# RasPi-BplusHAT.net
KiCad netlist of a schematic drawn in EAGLE
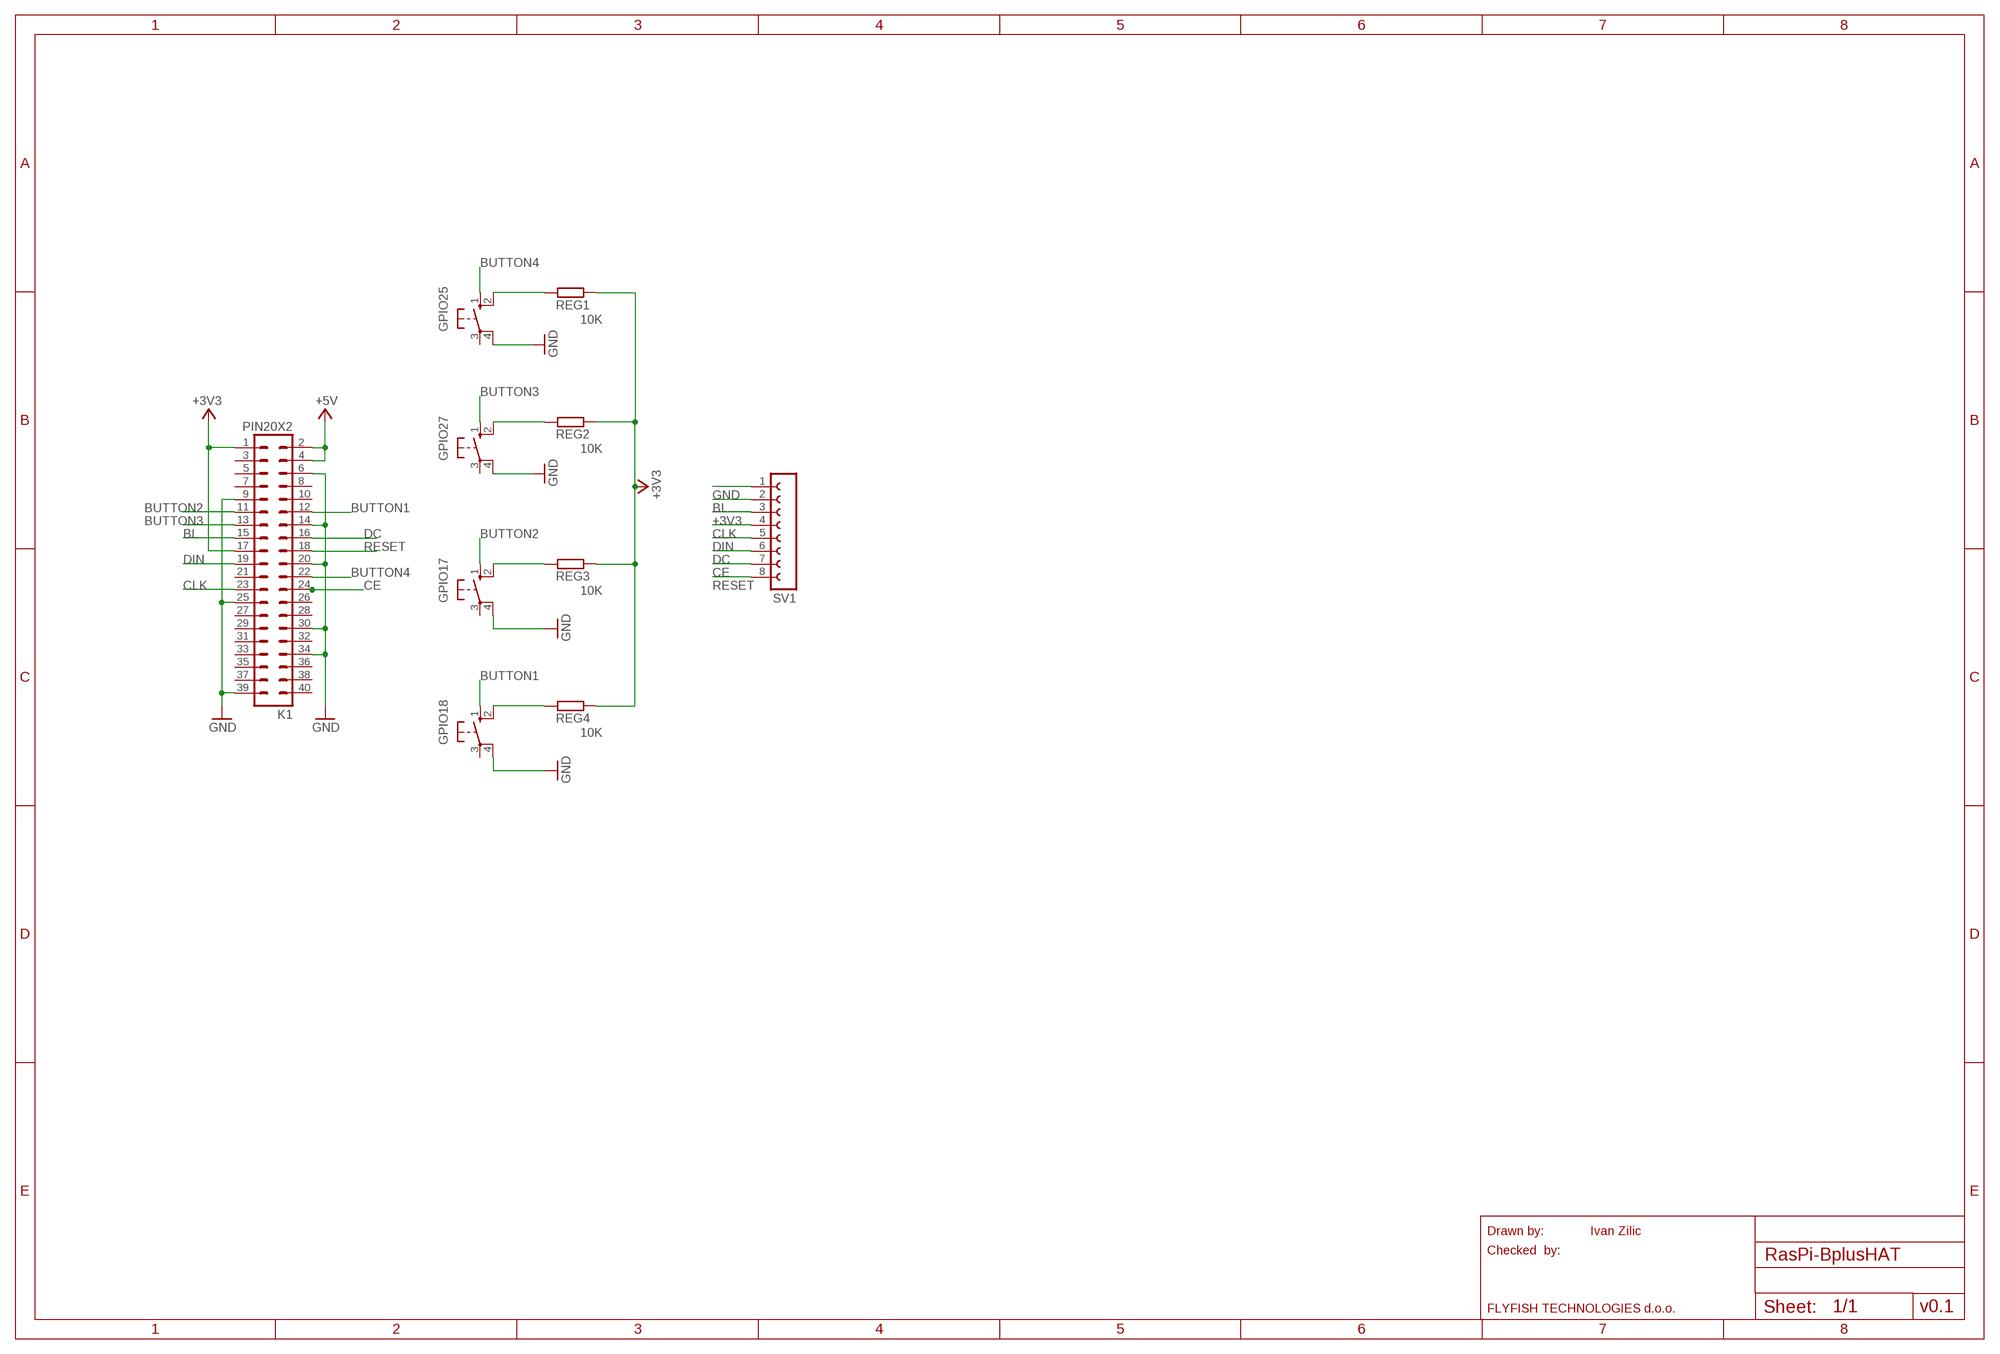
[diagram p0: schematic, sheet 1]

(export (version "E")
  (design (tool "Eeschema 10.0.6"))
  (components
    (comp (ref "GPIO17")
      (value "10-XX")
      (footprint "eagle-import:B3F-10XX")
      (fields (field (name "MPN") "B3F-1000"))
      (libsource (lib "eagle-import") (part "10-XX"))
    )
    (comp (ref "GPIO18")
      (value "10-XX")
      (footprint "eagle-import:B3F-10XX")
      (fields (field (name "MPN") "B3F-1000"))
      (libsource (lib "eagle-import") (part "10-XX"))
    )
    (comp (ref "GPIO25")
      (value "10-XX")
      (footprint "eagle-import:B3F-10XX")
      (fields (field (name "MPN") "B3F-1000"))
      (libsource (lib "eagle-import") (part "10-XX"))
    )
    (comp (ref "GPIO27")
      (value "10-XX")
      (footprint "eagle-import:B3F-10XX")
      (fields (field (name "MPN") "B3F-1000"))
      (libsource (lib "eagle-import") (part "10-XX"))
    )
    (comp (ref "K1")
      (value "PIN20X2")
      (footprint "eagle-import:PIN_20X2")
      (libsource (lib "eagle-import") (part "PIN20X2"))
    )
    (comp (ref "REG1")
      (value "10K")
      (footprint "eagle-import:0204_7")
      (libsource (lib "eagle-import") (part "R-EU_0204/7"))
    )
    (comp (ref "REG2")
      (value "10K")
      (footprint "eagle-import:0204_7")
      (libsource (lib "eagle-import") (part "R-EU_0204/7"))
    )
    (comp (ref "REG3")
      (value "10K")
      (footprint "eagle-import:0204_7")
      (libsource (lib "eagle-import") (part "R-EU_0204/7"))
    )
    (comp (ref "REG4")
      (value "10K")
      (footprint "eagle-import:0204_7")
      (libsource (lib "eagle-import") (part "R-EU_0204/7"))
    )
    (comp (ref "SV1")
      (value "FE08-1")
      (footprint "eagle-import:FE08")
      (libsource (lib "eagle-import") (part "FE08-1"))
    )
  )
  (nets
    (net (code "1") (name "+3V3") (class "Default")
      (node (ref "K1") (pin "1") (pinfunction "1_1") (pintype "passive"))
      (node (ref "K1") (pin "17") (pinfunction "17_17") (pintype "passive"))
      (node (ref "REG1") (pin "1") (pinfunction "1_1") (pintype "passive"))
      (node (ref "REG2") (pin "1") (pinfunction "1_1") (pintype "passive"))
      (node (ref "REG3") (pin "1") (pinfunction "1_1") (pintype "passive"))
      (node (ref "REG4") (pin "1") (pinfunction "1_1") (pintype "passive"))
      (node (ref "SV1") (pin "3") (pinfunction "3_3") (pintype "passive"))
    )
    (net (code "2") (name "+5V") (class "Default")
      (node (ref "K1") (pin "2") (pinfunction "2_2") (pintype "passive"))
      (node (ref "K1") (pin "4") (pinfunction "4_4") (pintype "passive"))
    )
    (net (code "3") (name "/BL") (class "Default")
      (node (ref "K1") (pin "15") (pinfunction "15_15") (pintype "passive"))
      (node (ref "SV1") (pin "2") (pinfunction "2_2") (pintype "passive"))
    )
    (net (code "4") (name "/BUTTON1") (class "Default")
      (node (ref "GPIO18") (pin "1") (pinfunction "S_1") (pintype "passive"))
      (node (ref "K1") (pin "12") (pinfunction "12_12") (pintype "passive"))
    )
    (net (code "5") (name "/BUTTON2") (class "Default")
      (node (ref "GPIO17") (pin "1") (pinfunction "S_1") (pintype "passive"))
      (node (ref "K1") (pin "11") (pinfunction "11_11") (pintype "passive"))
    )
    (net (code "6") (name "/BUTTON3") (class "Default")
      (node (ref "GPIO27") (pin "1") (pinfunction "S_1") (pintype "passive"))
      (node (ref "K1") (pin "13") (pinfunction "13_13") (pintype "passive"))
    )
    (net (code "7") (name "/BUTTON4") (class "Default")
      (node (ref "GPIO25") (pin "1") (pinfunction "S_1") (pintype "passive"))
      (node (ref "K1") (pin "22") (pinfunction "22_22") (pintype "passive"))
    )
    (net (code "8") (name "/CE") (class "Default")
      (node (ref "K1") (pin "24") (pinfunction "24_24") (pintype "passive"))
      (node (ref "SV1") (pin "7") (pinfunction "7_7") (pintype "passive"))
    )
    (net (code "9") (name "/CLK") (class "Default")
      (node (ref "K1") (pin "23") (pinfunction "23_23") (pintype "passive"))
      (node (ref "SV1") (pin "4") (pinfunction "4_4") (pintype "passive"))
    )
    (net (code "10") (name "/DC") (class "Default")
      (node (ref "K1") (pin "16") (pinfunction "16_16") (pintype "passive"))
      (node (ref "SV1") (pin "6") (pinfunction "6_6") (pintype "passive"))
    )
    (net (code "11") (name "/DIN") (class "Default")
      (node (ref "K1") (pin "19") (pinfunction "19_19") (pintype "passive"))
      (node (ref "SV1") (pin "5") (pinfunction "5_5") (pintype "passive"))
    )
    (net (code "12") (name "/RESET") (class "Default")
      (node (ref "K1") (pin "18") (pinfunction "18_18") (pintype "passive"))
      (node (ref "SV1") (pin "8") (pinfunction "8_8") (pintype "passive"))
    )
    (net (code "13") (name "GND") (class "Default")
      (node (ref "GPIO17") (pin "4") (pinfunction "P1_4") (pintype "passive"))
      (node (ref "GPIO18") (pin "4") (pinfunction "P1_4") (pintype "passive"))
      (node (ref "GPIO25") (pin "4") (pinfunction "P1_4") (pintype "passive"))
      (node (ref "GPIO27") (pin "4") (pinfunction "P1_4") (pintype "passive"))
      (node (ref "K1") (pin "14") (pinfunction "14_14") (pintype "passive"))
      (node (ref "K1") (pin "20") (pinfunction "20_20") (pintype "passive"))
      (node (ref "K1") (pin "25") (pinfunction "25_25") (pintype "passive"))
      (node (ref "K1") (pin "30") (pinfunction "30_30") (pintype "passive"))
      (node (ref "K1") (pin "34") (pinfunction "34_34") (pintype "passive"))
      (node (ref "K1") (pin "39") (pinfunction "39_39") (pintype "passive"))
      (node (ref "K1") (pin "6") (pinfunction "6_6") (pintype "passive"))
      (node (ref "K1") (pin "9") (pinfunction "9_9") (pintype "passive"))
      (node (ref "SV1") (pin "1") (pinfunction "1_1") (pintype "passive"))
    )
    (net (code "14") (name "Net-(GPIO17-S1)") (class "Default")
      (node (ref "GPIO17") (pin "2") (pinfunction "S1_2") (pintype "passive"))
      (node (ref "REG3") (pin "2") (pinfunction "2_2") (pintype "passive"))
    )
    (net (code "15") (name "Net-(GPIO18-S1)") (class "Default")
      (node (ref "GPIO18") (pin "2") (pinfunction "S1_2") (pintype "passive"))
      (node (ref "REG4") (pin "2") (pinfunction "2_2") (pintype "passive"))
    )
    (net (code "16") (name "Net-(GPIO25-S1)") (class "Default")
      (node (ref "GPIO25") (pin "2") (pinfunction "S1_2") (pintype "passive"))
      (node (ref "REG1") (pin "2") (pinfunction "2_2") (pintype "passive"))
    )
    (net (code "17") (name "Net-(GPIO27-S1)") (class "Default")
      (node (ref "GPIO27") (pin "2") (pinfunction "S1_2") (pintype "passive"))
      (node (ref "REG2") (pin "2") (pinfunction "2_2") (pintype "passive"))
    )
    (net (code "18") (name "unconnected-(GPIO17-P-Pad3)") (class "Default")
      (node (ref "GPIO17") (pin "3") (pinfunction "P_3") (pintype "passive"))
    )
    (net (code "19") (name "unconnected-(GPIO18-P-Pad3)") (class "Default")
      (node (ref "GPIO18") (pin "3") (pinfunction "P_3") (pintype "passive"))
    )
    (net (code "20") (name "unconnected-(GPIO25-P-Pad3)") (class "Default")
      (node (ref "GPIO25") (pin "3") (pinfunction "P_3") (pintype "passive"))
    )
    (net (code "21") (name "unconnected-(GPIO27-P-Pad3)") (class "Default")
      (node (ref "GPIO27") (pin "3") (pinfunction "P_3") (pintype "passive"))
    )
    (net (code "22") (name "unconnected-(K1-Pad3)") (class "Default")
      (node (ref "K1") (pin "3") (pinfunction "3_3") (pintype "passive"))
    )
    (net (code "23") (name "unconnected-(K1-Pad5)") (class "Default")
      (node (ref "K1") (pin "5") (pinfunction "5_5") (pintype "passive"))
    )
    (net (code "24") (name "unconnected-(K1-Pad7)") (class "Default")
      (node (ref "K1") (pin "7") (pinfunction "7_7") (pintype "passive"))
    )
    (net (code "25") (name "unconnected-(K1-Pad8)") (class "Default")
      (node (ref "K1") (pin "8") (pinfunction "8_8") (pintype "passive"))
    )
    (net (code "26") (name "unconnected-(K1-Pad10)") (class "Default")
      (node (ref "K1") (pin "10") (pinfunction "10_10") (pintype "passive"))
    )
    (net (code "27") (name "unconnected-(K1-Pad21)") (class "Default")
      (node (ref "K1") (pin "21") (pinfunction "21_21") (pintype "passive"))
    )
    (net (code "28") (name "unconnected-(K1-Pad26)") (class "Default")
      (node (ref "K1") (pin "26") (pinfunction "26_26") (pintype "passive"))
    )
    (net (code "29") (name "unconnected-(K1-Pad27)") (class "Default")
      (node (ref "K1") (pin "27") (pinfunction "27_27") (pintype "passive"))
    )
    (net (code "30") (name "unconnected-(K1-Pad28)") (class "Default")
      (node (ref "K1") (pin "28") (pinfunction "28_28") (pintype "passive"))
    )
    (net (code "31") (name "unconnected-(K1-Pad29)") (class "Default")
      (node (ref "K1") (pin "29") (pinfunction "29_29") (pintype "passive"))
    )
    (net (code "32") (name "unconnected-(K1-Pad31)") (class "Default")
      (node (ref "K1") (pin "31") (pinfunction "31_31") (pintype "passive"))
    )
    (net (code "33") (name "unconnected-(K1-Pad32)") (class "Default")
      (node (ref "K1") (pin "32") (pinfunction "32_32") (pintype "passive"))
    )
    (net (code "34") (name "unconnected-(K1-Pad33)") (class "Default")
      (node (ref "K1") (pin "33") (pinfunction "33_33") (pintype "passive"))
    )
    (net (code "35") (name "unconnected-(K1-Pad35)") (class "Default")
      (node (ref "K1") (pin "35") (pinfunction "35_35") (pintype "passive"))
    )
    (net (code "36") (name "unconnected-(K1-Pad36)") (class "Default")
      (node (ref "K1") (pin "36") (pinfunction "36_36") (pintype "passive"))
    )
    (net (code "37") (name "unconnected-(K1-Pad37)") (class "Default")
      (node (ref "K1") (pin "37") (pinfunction "37_37") (pintype "passive"))
    )
    (net (code "38") (name "unconnected-(K1-Pad38)") (class "Default")
      (node (ref "K1") (pin "38") (pinfunction "38_38") (pintype "passive"))
    )
    (net (code "39") (name "unconnected-(K1-Pad40)") (class "Default")
      (node (ref "K1") (pin "40") (pinfunction "40_40") (pintype "passive"))
    )
  )
)
